# PHOTODIODE_SENSOR.net
KiCad netlist of a schematic drawn in EAGLE
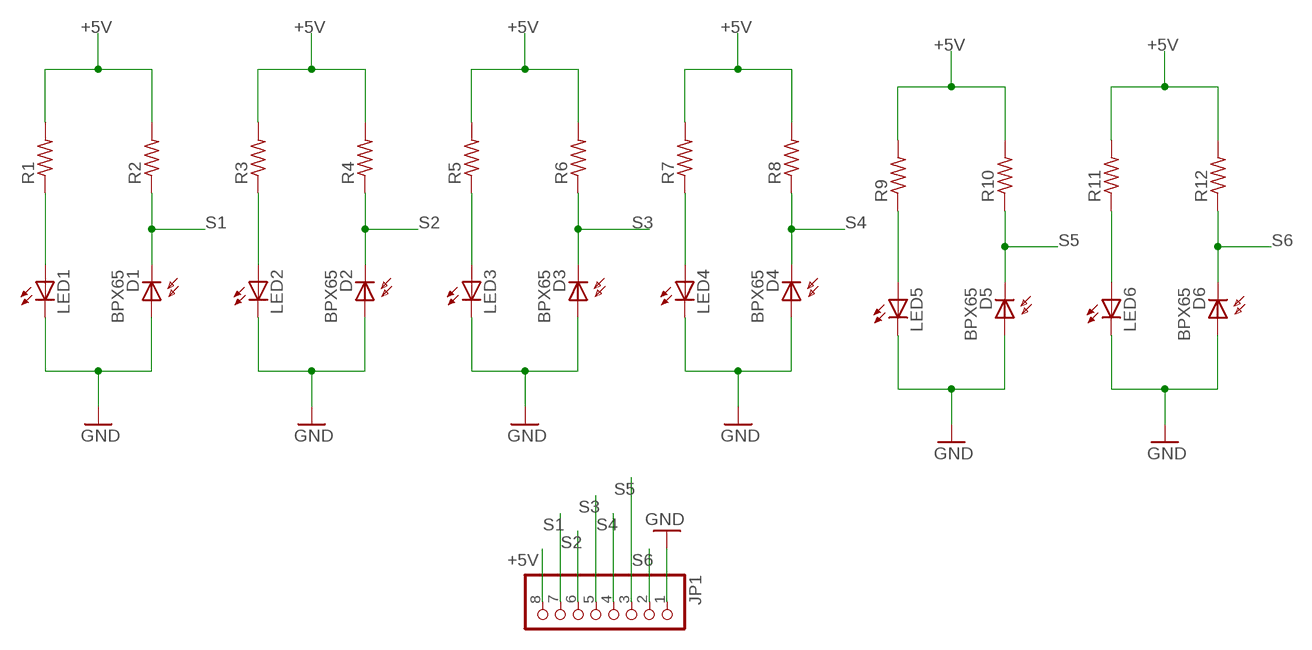
[diagram p0: schematic, sheet 1]

(export (version "E")
  (design (tool "Eeschema 10.0.6"))
  (components
    (comp (ref "D1")
      (value "BPX65")
      (footprint "eagle-import:BPX65")
      (fields (field (name "MPN") "BPX65."))
      (libsource (lib "eagle-import") (part "BPX65"))
    )
    (comp (ref "D2")
      (value "BPX65")
      (footprint "eagle-import:BPX65")
      (fields (field (name "MPN") "BPX65."))
      (libsource (lib "eagle-import") (part "BPX65"))
    )
    (comp (ref "D3")
      (value "BPX65")
      (footprint "eagle-import:BPX65")
      (fields (field (name "MPN") "BPX65."))
      (libsource (lib "eagle-import") (part "BPX65"))
    )
    (comp (ref "D4")
      (value "BPX65")
      (footprint "eagle-import:BPX65")
      (fields (field (name "MPN") "BPX65."))
      (libsource (lib "eagle-import") (part "BPX65"))
    )
    (comp (ref "D5")
      (value "BPX65")
      (footprint "eagle-import:BPX65")
      (fields (field (name "MPN") "BPX65."))
      (libsource (lib "eagle-import") (part "BPX65"))
    )
    (comp (ref "D6")
      (value "BPX65")
      (footprint "eagle-import:BPX65")
      (fields (field (name "MPN") "BPX65."))
      (libsource (lib "eagle-import") (part "BPX65"))
    )
    (comp (ref "JP1")
      (value "PINHD-1X8")
      (footprint "eagle-import:1X08")
      (libsource (lib "eagle-import") (part "PINHD-1X8"))
    )
    (comp (ref "LED1")
      (value "LED5MM")
      (footprint "eagle-import:LED5MM")
      (libsource (lib "eagle-import") (part "LED5MM"))
    )
    (comp (ref "LED2")
      (value "LED5MM")
      (footprint "eagle-import:LED5MM")
      (libsource (lib "eagle-import") (part "LED5MM"))
    )
    (comp (ref "LED3")
      (value "LED5MM")
      (footprint "eagle-import:LED5MM")
      (libsource (lib "eagle-import") (part "LED5MM"))
    )
    (comp (ref "LED4")
      (value "LED5MM")
      (footprint "eagle-import:LED5MM")
      (libsource (lib "eagle-import") (part "LED5MM"))
    )
    (comp (ref "LED5")
      (value "LED5MM")
      (footprint "eagle-import:LED5MM")
      (libsource (lib "eagle-import") (part "LED5MM"))
    )
    (comp (ref "LED6")
      (value "LED5MM")
      (footprint "eagle-import:LED5MM")
      (libsource (lib "eagle-import") (part "LED5MM"))
    )
    (comp (ref "R1")
      (value "R-US_0204/7")
      (footprint "eagle-import:0204_7")
      (libsource (lib "eagle-import") (part "R-US_0204/7"))
    )
    (comp (ref "R2")
      (value "R-US_0204/7")
      (footprint "eagle-import:0204_7")
      (libsource (lib "eagle-import") (part "R-US_0204/7"))
    )
    (comp (ref "R3")
      (value "R-US_0204/7")
      (footprint "eagle-import:0204_7")
      (libsource (lib "eagle-import") (part "R-US_0204/7"))
    )
    (comp (ref "R4")
      (value "R-US_0204/7")
      (footprint "eagle-import:0204_7")
      (libsource (lib "eagle-import") (part "R-US_0204/7"))
    )
    (comp (ref "R5")
      (value "R-US_0204/7")
      (footprint "eagle-import:0204_7")
      (libsource (lib "eagle-import") (part "R-US_0204/7"))
    )
    (comp (ref "R6")
      (value "R-US_0204/7")
      (footprint "eagle-import:0204_7")
      (libsource (lib "eagle-import") (part "R-US_0204/7"))
    )
    (comp (ref "R7")
      (value "R-US_0204/7")
      (footprint "eagle-import:0204_7")
      (libsource (lib "eagle-import") (part "R-US_0204/7"))
    )
    (comp (ref "R8")
      (value "R-US_0204/7")
      (footprint "eagle-import:0204_7")
      (libsource (lib "eagle-import") (part "R-US_0204/7"))
    )
    (comp (ref "R9")
      (value "R-US_0204/7")
      (footprint "eagle-import:0204_7")
      (libsource (lib "eagle-import") (part "R-US_0204/7"))
    )
    (comp (ref "R10")
      (value "R-US_0204/7")
      (footprint "eagle-import:0204_7")
      (libsource (lib "eagle-import") (part "R-US_0204/7"))
    )
    (comp (ref "R11")
      (value "R-US_0204/7")
      (footprint "eagle-import:0204_7")
      (libsource (lib "eagle-import") (part "R-US_0204/7"))
    )
    (comp (ref "R12")
      (value "R-US_0204/7")
      (footprint "eagle-import:0204_7")
      (libsource (lib "eagle-import") (part "R-US_0204/7"))
    )
  )
  (nets
    (net (code "1") (name "/+5V") (class "Default")
      (node (ref "JP1") (pin "8") (pinfunction "8_8") (pintype "passive"))
      (node (ref "R1") (pin "2") (pinfunction "2_2") (pintype "passive"))
      (node (ref "R10") (pin "2") (pinfunction "2_2") (pintype "passive"))
      (node (ref "R11") (pin "2") (pinfunction "2_2") (pintype "passive"))
      (node (ref "R12") (pin "2") (pinfunction "2_2") (pintype "passive"))
      (node (ref "R2") (pin "2") (pinfunction "2_2") (pintype "passive"))
      (node (ref "R3") (pin "2") (pinfunction "2_2") (pintype "passive"))
      (node (ref "R4") (pin "2") (pinfunction "2_2") (pintype "passive"))
      (node (ref "R5") (pin "2") (pinfunction "2_2") (pintype "passive"))
      (node (ref "R6") (pin "2") (pinfunction "2_2") (pintype "passive"))
      (node (ref "R7") (pin "2") (pinfunction "2_2") (pintype "passive"))
      (node (ref "R8") (pin "2") (pinfunction "2_2") (pintype "passive"))
      (node (ref "R9") (pin "2") (pinfunction "2_2") (pintype "passive"))
    )
    (net (code "2") (name "/S1") (class "Default")
      (node (ref "D1") (pin "K") (pinfunction "C_K") (pintype "passive"))
      (node (ref "JP1") (pin "7") (pinfunction "7_7") (pintype "passive"))
      (node (ref "R2") (pin "1") (pinfunction "1_1") (pintype "passive"))
    )
    (net (code "3") (name "/S2") (class "Default")
      (node (ref "D2") (pin "K") (pinfunction "C_K") (pintype "passive"))
      (node (ref "JP1") (pin "6") (pinfunction "6_6") (pintype "passive"))
      (node (ref "R4") (pin "1") (pinfunction "1_1") (pintype "passive"))
    )
    (net (code "4") (name "/S3") (class "Default")
      (node (ref "D3") (pin "K") (pinfunction "C_K") (pintype "passive"))
      (node (ref "JP1") (pin "5") (pinfunction "5_5") (pintype "passive"))
      (node (ref "R6") (pin "1") (pinfunction "1_1") (pintype "passive"))
    )
    (net (code "5") (name "/S4") (class "Default")
      (node (ref "D4") (pin "K") (pinfunction "C_K") (pintype "passive"))
      (node (ref "JP1") (pin "4") (pinfunction "4_4") (pintype "passive"))
      (node (ref "R8") (pin "1") (pinfunction "1_1") (pintype "passive"))
    )
    (net (code "6") (name "/S5") (class "Default")
      (node (ref "D5") (pin "K") (pinfunction "C_K") (pintype "passive"))
      (node (ref "JP1") (pin "3") (pinfunction "3_3") (pintype "passive"))
      (node (ref "R10") (pin "1") (pinfunction "1_1") (pintype "passive"))
    )
    (net (code "7") (name "/S6") (class "Default")
      (node (ref "D6") (pin "K") (pinfunction "C_K") (pintype "passive"))
      (node (ref "JP1") (pin "2") (pinfunction "2_2") (pintype "passive"))
      (node (ref "R12") (pin "1") (pinfunction "1_1") (pintype "passive"))
    )
    (net (code "8") (name "GND") (class "Default")
      (node (ref "D1") (pin "A") (pinfunction "A_A") (pintype "passive"))
      (node (ref "D2") (pin "A") (pinfunction "A_A") (pintype "passive"))
      (node (ref "D3") (pin "A") (pinfunction "A_A") (pintype "passive"))
      (node (ref "D4") (pin "A") (pinfunction "A_A") (pintype "passive"))
      (node (ref "D5") (pin "A") (pinfunction "A_A") (pintype "passive"))
      (node (ref "D6") (pin "A") (pinfunction "A_A") (pintype "passive"))
      (node (ref "JP1") (pin "1") (pinfunction "1_1") (pintype "passive"))
      (node (ref "LED1") (pin "K") (pinfunction "C_K") (pintype "passive"))
      (node (ref "LED2") (pin "K") (pinfunction "C_K") (pintype "passive"))
      (node (ref "LED3") (pin "K") (pinfunction "C_K") (pintype "passive"))
      (node (ref "LED4") (pin "K") (pinfunction "C_K") (pintype "passive"))
      (node (ref "LED5") (pin "K") (pinfunction "C_K") (pintype "passive"))
      (node (ref "LED6") (pin "K") (pinfunction "C_K") (pintype "passive"))
    )
    (net (code "9") (name "Net-(LED1-PadA)") (class "Default")
      (node (ref "LED1") (pin "A") (pinfunction "A_A") (pintype "passive"))
      (node (ref "R1") (pin "1") (pinfunction "1_1") (pintype "passive"))
    )
    (net (code "10") (name "Net-(LED2-PadA)") (class "Default")
      (node (ref "LED2") (pin "A") (pinfunction "A_A") (pintype "passive"))
      (node (ref "R3") (pin "1") (pinfunction "1_1") (pintype "passive"))
    )
    (net (code "11") (name "Net-(LED3-PadA)") (class "Default")
      (node (ref "LED3") (pin "A") (pinfunction "A_A") (pintype "passive"))
      (node (ref "R5") (pin "1") (pinfunction "1_1") (pintype "passive"))
    )
    (net (code "12") (name "Net-(LED4-PadA)") (class "Default")
      (node (ref "LED4") (pin "A") (pinfunction "A_A") (pintype "passive"))
      (node (ref "R7") (pin "1") (pinfunction "1_1") (pintype "passive"))
    )
    (net (code "13") (name "Net-(LED5-PadA)") (class "Default")
      (node (ref "LED5") (pin "A") (pinfunction "A_A") (pintype "passive"))
      (node (ref "R9") (pin "1") (pinfunction "1_1") (pintype "passive"))
    )
    (net (code "14") (name "Net-(LED6-PadA)") (class "Default")
      (node (ref "LED6") (pin "A") (pinfunction "A_A") (pintype "passive"))
      (node (ref "R11") (pin "1") (pinfunction "1_1") (pintype "passive"))
    )
  )
)
